# Sheet1.net
KiCad netlist of a schematic drawn in Altium Designer
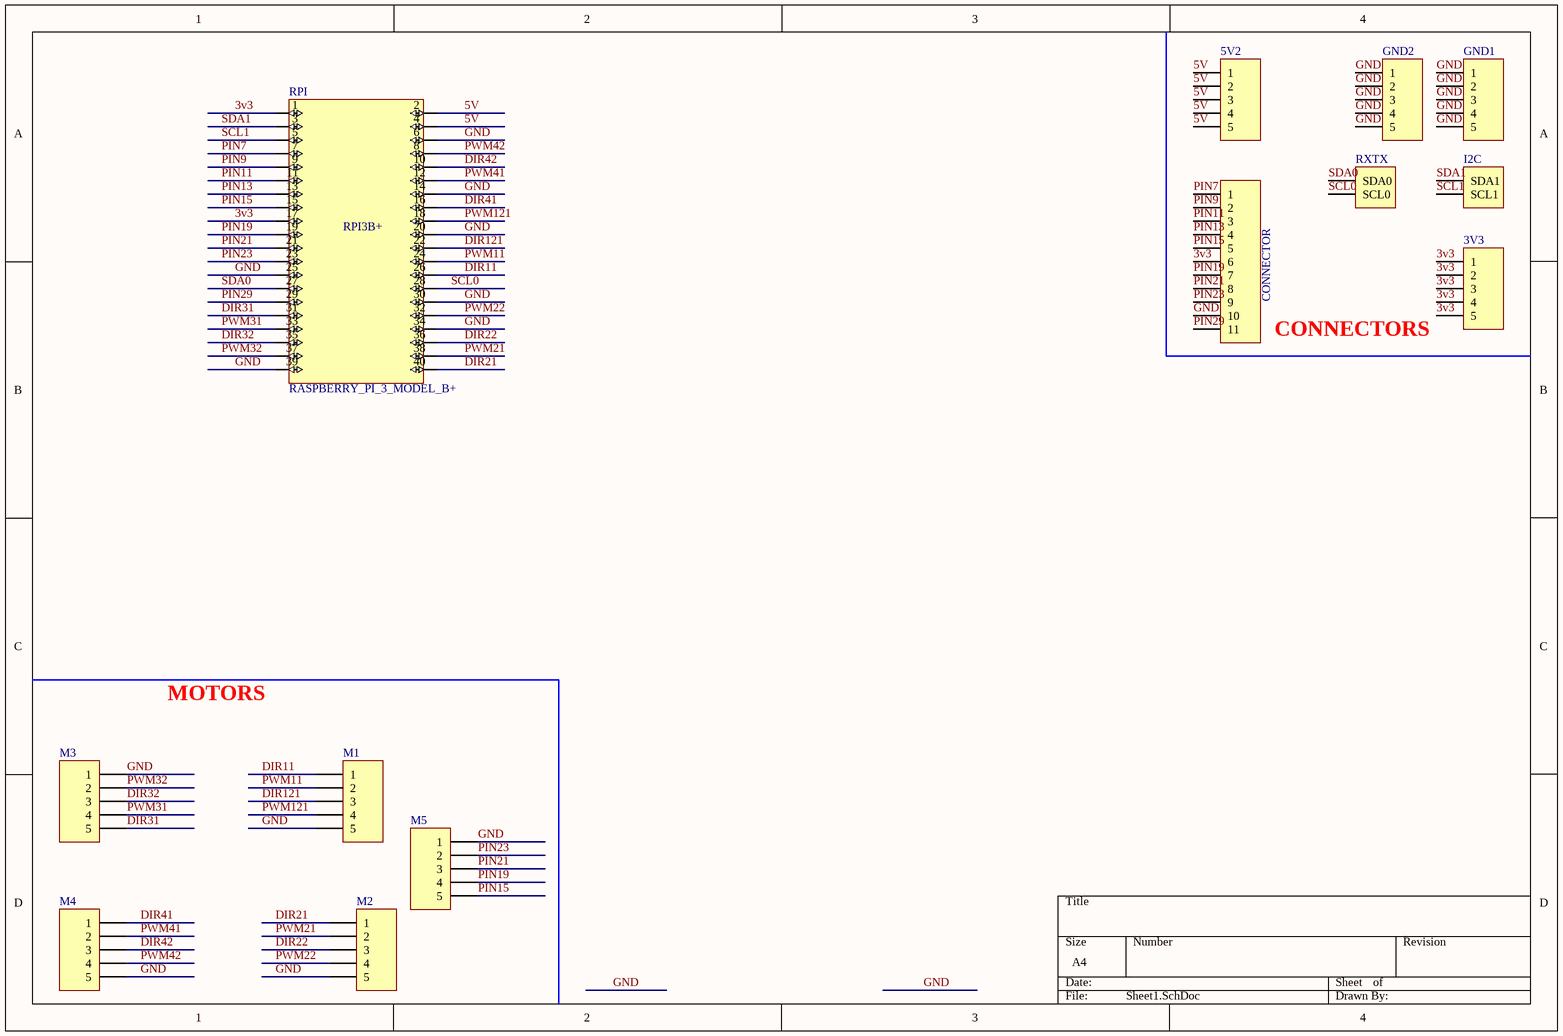
[diagram p0: Sheet1.SchDoc]

(export (version "E")
  (design (tool "Eeschema 10.0.6"))
  (components
    (comp (ref "3V3")
      (value "Header 5")
      (footprint "HDR1X5")
      (description "Header, 5-Pin")
      (fields (field (name "PUBLISHER") "Altium Limited"))
      (libsource (lib "Miscellaneous Connectors") (part "Header 5"))
    )
    (comp (ref "5V2")
      (value "Header 5")
      (footprint "HDR1X5")
      (description "Header, 5-Pin")
      (fields (field (name "PUBLISHER") "Altium Limited"))
      (libsource (lib "Miscellaneous Connectors") (part "Header 5"))
    )
    (comp (ref "CONNECTOR")
      (value "Header 11")
      (footprint "HDR1X11")
      (description "Header, 11-Pin")
      (fields (field (name "PUBLISHER") "Altium Limited"))
      (libsource (lib "Miscellaneous Connectors") (part "Header 11"))
    )
    (comp (ref "GND1")
      (value "Header 5")
      (footprint "HDR1X5")
      (description "Header, 5-Pin")
      (fields (field (name "PUBLISHER") "Altium Limited"))
      (libsource (lib "Miscellaneous Connectors") (part "Header 5"))
    )
    (comp (ref "GND2")
      (value "Header 5")
      (footprint "HDR1X5")
      (description "Header, 5-Pin")
      (fields (field (name "PUBLISHER") "Altium Limited"))
      (libsource (lib "Miscellaneous Connectors") (part "Header 5"))
    )
    (comp (ref "I2C")
      (value "Header 2")
      (footprint "HDR1X2")
      (description "Header, 2-Pin")
      (fields (field (name "PUBLISHER") "Altium Limited"))
      (libsource (lib "Miscellaneous Connectors") (part "Header 2"))
    )
    (comp (ref "M1")
      (value "Header 5")
      (footprint "HDR1X5")
      (description "Header, 5-Pin")
      (fields (field (name "PUBLISHER") "Altium Limited"))
      (libsource (lib "Miscellaneous Connectors") (part "Header 5"))
    )
    (comp (ref "M2")
      (value "Header 5")
      (footprint "HDR1X5")
      (description "Header, 5-Pin")
      (fields (field (name "PUBLISHER") "Altium Limited"))
      (libsource (lib "Miscellaneous Connectors") (part "Header 5"))
    )
    (comp (ref "M3")
      (value "Header 5")
      (footprint "HDR1X5")
      (description "Header, 5-Pin")
      (fields (field (name "PUBLISHER") "Altium Limited"))
      (libsource (lib "") (part "Header 5_1"))
    )
    (comp (ref "M4")
      (value "Header 5")
      (footprint "HDR1X5")
      (description "Header, 5-Pin")
      (fields (field (name "PUBLISHER") "Altium Limited"))
      (libsource (lib "") (part "Header 5_1"))
    )
    (comp (ref "M5")
      (value "Header 5")
      (footprint "HDR1X5")
      (description "Header, 5-Pin")
      (fields (field (name "PUBLISHER") "Altium Limited"))
      (libsource (lib "") (part "Header 5_1"))
    )
    (comp (ref "RPI")
      (value "RASPBERRY_PI_3_MODEL_B+")
      (footprint "MODULE_RASPBERRY_PI_3_MODEL_B+")
      (fields (field (name "MF") "Raspberry Pi") (field (name "MP") "RASPBERRY PI 3 MODEL B+"))
      (libsource (lib "RASPBERRY_PI_3_MODEL_B+") (part "RASPBERRY_PI_3_MODEL_B+"))
    )
    (comp (ref "RXTX")
      (value "Header 2")
      (footprint "HDR1X2")
      (description "Header, 2-Pin")
      (fields (field (name "PUBLISHER") "Altium Limited"))
      (libsource (lib "Miscellaneous Connectors") (part "Header 2"))
    )
  )
  (nets
    (net (code "1") (name "/3v3") (class "Default")
      (node (ref "3V3") (pin "1") (pinfunction "1_1") (pintype "passive"))
      (node (ref "3V3") (pin "2") (pinfunction "2_2") (pintype "passive"))
      (node (ref "3V3") (pin "3") (pinfunction "3_3") (pintype "passive"))
      (node (ref "3V3") (pin "4") (pinfunction "4_4") (pintype "passive"))
      (node (ref "3V3") (pin "5") (pinfunction "5_5") (pintype "passive"))
      (node (ref "CONNECTOR") (pin "6") (pinfunction "6_6") (pintype "passive"))
      (node (ref "RPI") (pin "1") (pinfunction "1_1") (pintype "bidirectional"))
      (node (ref "RPI") (pin "17") (pinfunction "17_17") (pintype "bidirectional"))
    )
    (net (code "2") (name "/5V") (class "Default")
      (node (ref "5V2") (pin "1") (pinfunction "1_1") (pintype "passive"))
      (node (ref "5V2") (pin "2") (pinfunction "2_2") (pintype "passive"))
      (node (ref "5V2") (pin "3") (pinfunction "3_3") (pintype "passive"))
      (node (ref "5V2") (pin "4") (pinfunction "4_4") (pintype "passive"))
      (node (ref "5V2") (pin "5") (pinfunction "5_5") (pintype "passive"))
      (node (ref "RPI") (pin "2") (pinfunction "2_2") (pintype "bidirectional"))
      (node (ref "RPI") (pin "4") (pinfunction "4_4") (pintype "bidirectional"))
    )
    (net (code "3") (name "/DIR11") (class "Default")
      (node (ref "M1") (pin "1") (pinfunction "1_1") (pintype "passive"))
      (node (ref "RPI") (pin "26") (pinfunction "26_26") (pintype "bidirectional"))
    )
    (net (code "4") (name "/DIR21") (class "Default")
      (node (ref "M2") (pin "1") (pinfunction "1_1") (pintype "passive"))
      (node (ref "RPI") (pin "40") (pinfunction "40_40") (pintype "bidirectional"))
    )
    (net (code "5") (name "/DIR22") (class "Default")
      (node (ref "M2") (pin "3") (pinfunction "3_3") (pintype "passive"))
      (node (ref "RPI") (pin "36") (pinfunction "36_36") (pintype "bidirectional"))
    )
    (net (code "6") (name "/DIR31") (class "Default")
      (node (ref "M3") (pin "5") (pinfunction "5_5") (pintype "passive"))
      (node (ref "RPI") (pin "31") (pinfunction "31_31") (pintype "bidirectional"))
    )
    (net (code "7") (name "/DIR32") (class "Default")
      (node (ref "M3") (pin "3") (pinfunction "3_3") (pintype "passive"))
      (node (ref "RPI") (pin "35") (pinfunction "35_35") (pintype "bidirectional"))
    )
    (net (code "8") (name "/DIR41") (class "Default")
      (node (ref "M4") (pin "1") (pinfunction "1_1") (pintype "passive"))
      (node (ref "RPI") (pin "16") (pinfunction "16_16") (pintype "bidirectional"))
    )
    (net (code "9") (name "/DIR42") (class "Default")
      (node (ref "M4") (pin "3") (pinfunction "3_3") (pintype "passive"))
      (node (ref "RPI") (pin "10") (pinfunction "10_10") (pintype "bidirectional"))
    )
    (net (code "10") (name "/DIR121") (class "Default")
      (node (ref "M1") (pin "3") (pinfunction "3_3") (pintype "passive"))
      (node (ref "RPI") (pin "22") (pinfunction "22_22") (pintype "bidirectional"))
    )
    (net (code "11") (name "/GND") (class "Default")
      (node (ref "CONNECTOR") (pin "10") (pinfunction "10_10") (pintype "passive"))
      (node (ref "GND1") (pin "1") (pinfunction "1_1") (pintype "passive"))
      (node (ref "GND1") (pin "2") (pinfunction "2_2") (pintype "passive"))
      (node (ref "GND1") (pin "3") (pinfunction "3_3") (pintype "passive"))
      (node (ref "GND1") (pin "4") (pinfunction "4_4") (pintype "passive"))
      (node (ref "GND1") (pin "5") (pinfunction "5_5") (pintype "passive"))
      (node (ref "GND2") (pin "1") (pinfunction "1_1") (pintype "passive"))
      (node (ref "GND2") (pin "2") (pinfunction "2_2") (pintype "passive"))
      (node (ref "GND2") (pin "3") (pinfunction "3_3") (pintype "passive"))
      (node (ref "GND2") (pin "4") (pinfunction "4_4") (pintype "passive"))
      (node (ref "GND2") (pin "5") (pinfunction "5_5") (pintype "passive"))
      (node (ref "M1") (pin "5") (pinfunction "5_5") (pintype "passive"))
      (node (ref "M2") (pin "5") (pinfunction "5_5") (pintype "passive"))
      (node (ref "M3") (pin "1") (pinfunction "1_1") (pintype "passive"))
      (node (ref "M4") (pin "5") (pinfunction "5_5") (pintype "passive"))
      (node (ref "M5") (pin "1") (pinfunction "1_1") (pintype "passive"))
      (node (ref "RPI") (pin "14") (pinfunction "14_14") (pintype "bidirectional"))
      (node (ref "RPI") (pin "20") (pinfunction "20_20") (pintype "bidirectional"))
      (node (ref "RPI") (pin "25") (pinfunction "25_25") (pintype "bidirectional"))
      (node (ref "RPI") (pin "30") (pinfunction "30_30") (pintype "bidirectional"))
      (node (ref "RPI") (pin "34") (pinfunction "34_34") (pintype "bidirectional"))
      (node (ref "RPI") (pin "39") (pinfunction "39_39") (pintype "bidirectional"))
      (node (ref "RPI") (pin "6") (pinfunction "6_6") (pintype "bidirectional"))
    )
    (net (code "12") (name "/PIN7") (class "Default")
      (node (ref "CONNECTOR") (pin "1") (pinfunction "1_1") (pintype "passive"))
      (node (ref "RPI") (pin "7") (pinfunction "7_7") (pintype "bidirectional"))
    )
    (net (code "13") (name "/PIN9") (class "Default")
      (node (ref "CONNECTOR") (pin "2") (pinfunction "2_2") (pintype "passive"))
      (node (ref "RPI") (pin "9") (pinfunction "9_9") (pintype "bidirectional"))
    )
    (net (code "14") (name "/PIN11") (class "Default")
      (node (ref "CONNECTOR") (pin "3") (pinfunction "3_3") (pintype "passive"))
      (node (ref "RPI") (pin "11") (pinfunction "11_11") (pintype "bidirectional"))
    )
    (net (code "15") (name "/PIN13") (class "Default")
      (node (ref "CONNECTOR") (pin "4") (pinfunction "4_4") (pintype "passive"))
      (node (ref "RPI") (pin "13") (pinfunction "13_13") (pintype "bidirectional"))
    )
    (net (code "16") (name "/PIN15") (class "Default")
      (node (ref "CONNECTOR") (pin "5") (pinfunction "5_5") (pintype "passive"))
      (node (ref "M5") (pin "5") (pinfunction "5_5") (pintype "passive"))
      (node (ref "RPI") (pin "15") (pinfunction "15_15") (pintype "bidirectional"))
    )
    (net (code "17") (name "/PIN19") (class "Default")
      (node (ref "CONNECTOR") (pin "7") (pinfunction "7_7") (pintype "passive"))
      (node (ref "M5") (pin "4") (pinfunction "4_4") (pintype "passive"))
      (node (ref "RPI") (pin "19") (pinfunction "19_19") (pintype "bidirectional"))
    )
    (net (code "18") (name "/PIN21") (class "Default")
      (node (ref "CONNECTOR") (pin "8") (pinfunction "8_8") (pintype "passive"))
      (node (ref "M5") (pin "3") (pinfunction "3_3") (pintype "passive"))
      (node (ref "RPI") (pin "21") (pinfunction "21_21") (pintype "bidirectional"))
    )
    (net (code "19") (name "/PIN23") (class "Default")
      (node (ref "CONNECTOR") (pin "9") (pinfunction "9_9") (pintype "passive"))
      (node (ref "M5") (pin "2") (pinfunction "2_2") (pintype "passive"))
      (node (ref "RPI") (pin "23") (pinfunction "23_23") (pintype "bidirectional"))
    )
    (net (code "20") (name "/PIN29") (class "Default")
      (node (ref "CONNECTOR") (pin "11") (pinfunction "11_11") (pintype "passive"))
      (node (ref "RPI") (pin "29") (pinfunction "29_29") (pintype "bidirectional"))
    )
    (net (code "21") (name "/PWM11") (class "Default")
      (node (ref "M1") (pin "2") (pinfunction "2_2") (pintype "passive"))
      (node (ref "RPI") (pin "24") (pinfunction "24_24") (pintype "bidirectional"))
    )
    (net (code "22") (name "/PWM21") (class "Default")
      (node (ref "M2") (pin "2") (pinfunction "2_2") (pintype "passive"))
      (node (ref "RPI") (pin "38") (pinfunction "38_38") (pintype "bidirectional"))
    )
    (net (code "23") (name "/PWM22") (class "Default")
      (node (ref "M2") (pin "4") (pinfunction "4_4") (pintype "passive"))
      (node (ref "RPI") (pin "32") (pinfunction "32_32") (pintype "bidirectional"))
    )
    (net (code "24") (name "/PWM31") (class "Default")
      (node (ref "M3") (pin "4") (pinfunction "4_4") (pintype "passive"))
      (node (ref "RPI") (pin "33") (pinfunction "33_33") (pintype "bidirectional"))
    )
    (net (code "25") (name "/PWM32") (class "Default")
      (node (ref "M3") (pin "2") (pinfunction "2_2") (pintype "passive"))
      (node (ref "RPI") (pin "37") (pinfunction "37_37") (pintype "bidirectional"))
    )
    (net (code "26") (name "/PWM41") (class "Default")
      (node (ref "M4") (pin "2") (pinfunction "2_2") (pintype "passive"))
      (node (ref "RPI") (pin "12") (pinfunction "12_12") (pintype "bidirectional"))
    )
    (net (code "27") (name "/PWM42") (class "Default")
      (node (ref "M4") (pin "4") (pinfunction "4_4") (pintype "passive"))
      (node (ref "RPI") (pin "8") (pinfunction "8_8") (pintype "bidirectional"))
    )
    (net (code "28") (name "/PWM121") (class "Default")
      (node (ref "M1") (pin "4") (pinfunction "4_4") (pintype "passive"))
      (node (ref "RPI") (pin "18") (pinfunction "18_18") (pintype "bidirectional"))
    )
    (net (code "29") (name "/SCL0") (class "Default")
      (node (ref "RPI") (pin "28") (pinfunction "28_28") (pintype "bidirectional"))
      (node (ref "RXTX") (pin "2") (pinfunction "SCL0_2") (pintype "passive"))
    )
    (net (code "30") (name "/SCL1") (class "Default")
      (node (ref "I2C") (pin "2") (pinfunction "SCL0_2") (pintype "passive"))
      (node (ref "RPI") (pin "5") (pinfunction "5_5") (pintype "bidirectional"))
    )
    (net (code "31") (name "/SDA0") (class "Default")
      (node (ref "RPI") (pin "27") (pinfunction "27_27") (pintype "bidirectional"))
      (node (ref "RXTX") (pin "1") (pinfunction "SDA0_1") (pintype "passive"))
    )
    (net (code "32") (name "/SDA1") (class "Default")
      (node (ref "I2C") (pin "1") (pinfunction "SDA0_1") (pintype "passive"))
      (node (ref "RPI") (pin "3") (pinfunction "3_3") (pintype "bidirectional"))
    )
  )
)
